# Sheet_4_nizovie.net
KiCad netlist of a schematic drawn in Altium Designer
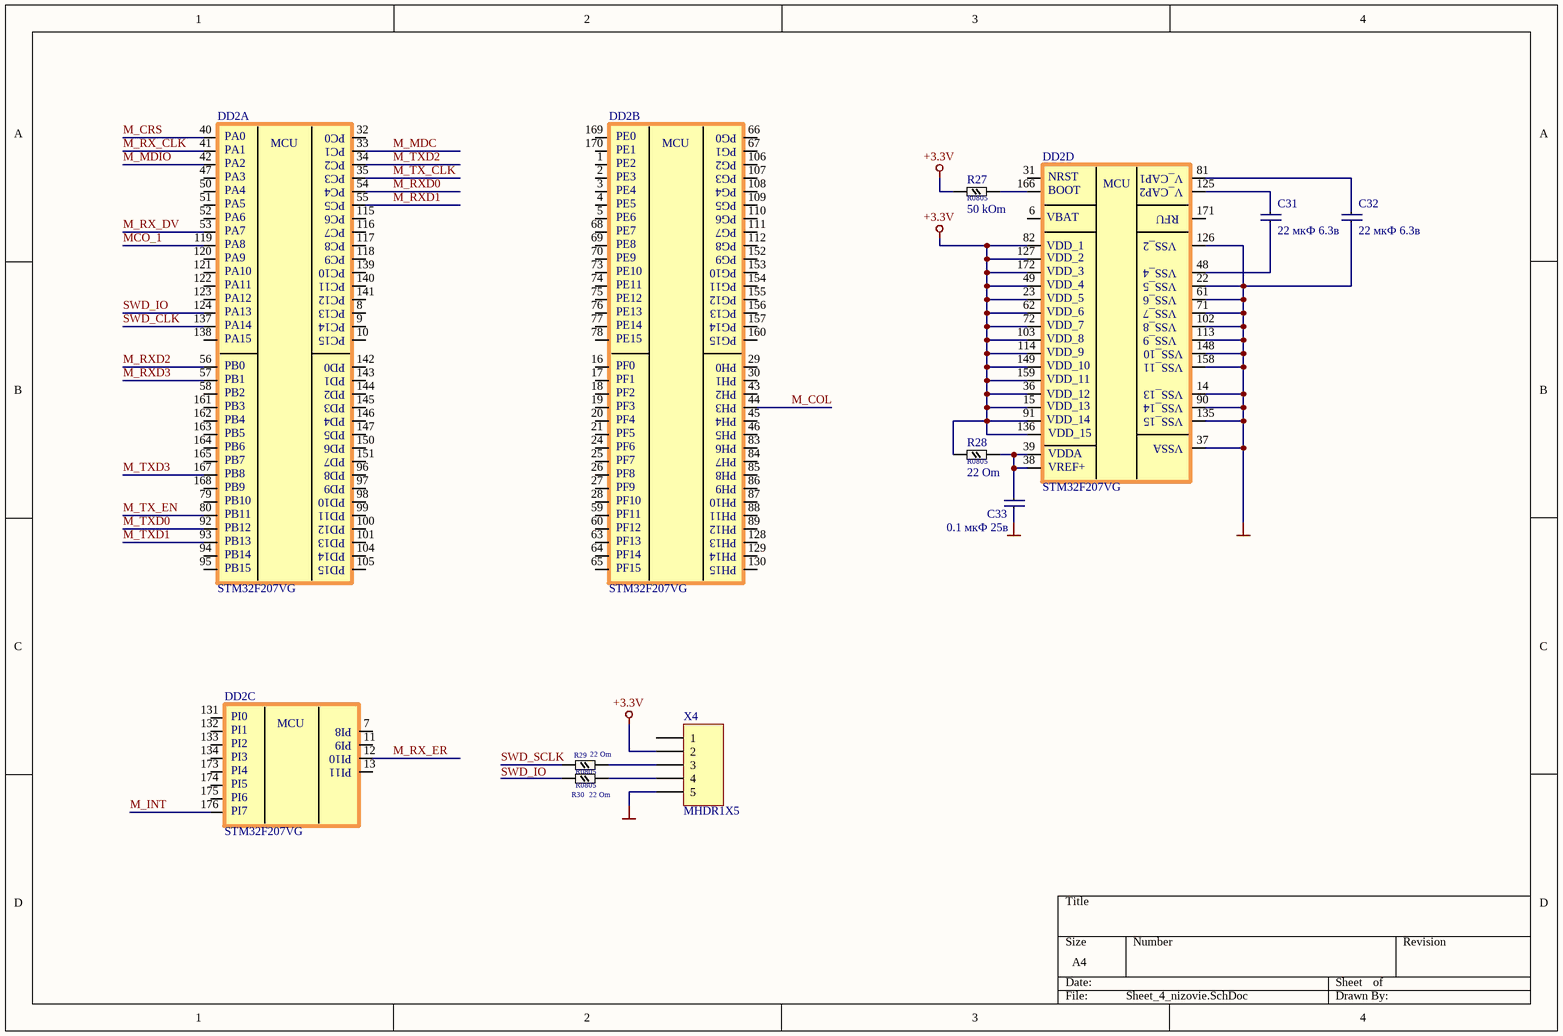
[diagram p0: Sheet_4_nizovie.SchDoc]

(export (version "E")
  (design (tool "Eeschema 10.0.6"))
  (components
    (comp (ref "C31")
      (value "22 мкФ 6.3в")
      (footprint "FP_0805")
      (libsource (lib "Schlib_nizovie") (part "C0805"))
    )
    (comp (ref "C32")
      (value "22 мкФ 6.3в")
      (footprint "FP_0805")
      (libsource (lib "Schlib_nizovie") (part "C0805"))
    )
    (comp (ref "C33")
      (value "0.1 мкФ 25в")
      (footprint "FP_0805")
      (libsource (lib "Schlib_nizovie") (part "C0805"))
    )
    (comp (ref "DD2")
      (value "STM32F207VG")
      (footprint "TSQFP50P2600X2600X160-176N")
      (description "STM32")
      (libsource (lib "Schlib_nizovie") (part "STM32D207VG"))
    )
    (comp (ref "R27")
      (value "50 kOm")
      (footprint "FP_0805")
      (libsource (lib "Schlib_nizovie") (part "R0805"))
    )
    (comp (ref "R28") (value "22 Om") (footprint "FP_0805") (libsource (lib "Schlib_nizovie") (part "R0805")))
    (comp (ref "R29") (value "22 Om") (footprint "FP_0805") (libsource (lib "Schlib_nizovie") (part "R0805")))
    (comp (ref "R30") (value "22 Om") (footprint "FP_0805") (libsource (lib "Schlib_nizovie") (part "R0805")))
    (comp (ref "X4")
      (value "MHDR1X5")
      (footprint "MHDR1X5")
      (description "Header, 5-Pin")
      (fields (field (name "PUBLISHER") "Altium Limited"))
      (libsource (lib "Miscellaneous Connectors") (part "MHDR1X5"))
    )
  )
  (nets
    (net (code "1") (name "+3.3V") (class "Default")
      (node (ref "DD2") (pin "103") (pinfunction "103_103") (pintype "passive"))
      (node (ref "DD2") (pin "114") (pinfunction "114_114") (pintype "passive"))
      (node (ref "DD2") (pin "127") (pinfunction "127_127") (pintype "passive"))
      (node (ref "DD2") (pin "136") (pinfunction "136_136") (pintype "passive"))
      (node (ref "DD2") (pin "149") (pinfunction "149_149") (pintype "passive"))
      (node (ref "DD2") (pin "15") (pinfunction "15_15") (pintype "passive"))
      (node (ref "DD2") (pin "159") (pinfunction "159_159") (pintype "passive"))
      (node (ref "DD2") (pin "172") (pinfunction "172_172") (pintype "passive"))
      (node (ref "DD2") (pin "23") (pinfunction "23_23") (pintype "passive"))
      (node (ref "DD2") (pin "36") (pinfunction "36_36") (pintype "passive"))
      (node (ref "DD2") (pin "49") (pinfunction "49_49") (pintype "passive"))
      (node (ref "DD2") (pin "62") (pinfunction "62_62") (pintype "passive"))
      (node (ref "DD2") (pin "72") (pinfunction "72_72") (pintype "passive"))
      (node (ref "DD2") (pin "82") (pinfunction "82_82") (pintype "passive"))
      (node (ref "DD2") (pin "91") (pinfunction "91_91") (pintype "passive"))
      (node (ref "R27") (pin "1") (pinfunction "1_1") (pintype "passive"))
      (node (ref "R28") (pin "1") (pinfunction "1_1") (pintype "passive"))
      (node (ref "X4") (pin "2") (pinfunction "2_2") (pintype "passive"))
    )
    (net (code "2") (name "/MCO_1") (class "Default")
      (node (ref "DD2") (pin "119") (pinfunction "119_119") (pintype "passive"))
    )
    (net (code "3") (name "/M_COL") (class "Default")
      (node (ref "DD2") (pin "44") (pinfunction "44_44") (pintype "passive"))
    )
    (net (code "4") (name "/M_CRS") (class "Default")
      (node (ref "DD2") (pin "40") (pinfunction "40_40") (pintype "passive"))
    )
    (net (code "5") (name "/M_INT") (class "Default")
      (node (ref "DD2") (pin "176") (pinfunction "176_176") (pintype "passive"))
    )
    (net (code "6") (name "/M_MDC") (class "Default")
      (node (ref "DD2") (pin "33") (pinfunction "33_33") (pintype "passive"))
    )
    (net (code "7") (name "/M_MDIO") (class "Default")
      (node (ref "DD2") (pin "42") (pinfunction "42_42") (pintype "passive"))
    )
    (net (code "8") (name "/M_RXD0") (class "Default")
      (node (ref "DD2") (pin "54") (pinfunction "54_54") (pintype "passive"))
    )
    (net (code "9") (name "/M_RXD1") (class "Default")
      (node (ref "DD2") (pin "55") (pinfunction "55_55") (pintype "passive"))
    )
    (net (code "10") (name "/M_RXD2") (class "Default")
      (node (ref "DD2") (pin "56") (pinfunction "56_56") (pintype "passive"))
    )
    (net (code "11") (name "/M_RXD3") (class "Default")
      (node (ref "DD2") (pin "57") (pinfunction "57_57") (pintype "passive"))
    )
    (net (code "12") (name "/M_RX_CLK") (class "Default")
      (node (ref "DD2") (pin "41") (pinfunction "41_41") (pintype "passive"))
    )
    (net (code "13") (name "/M_RX_DV") (class "Default")
      (node (ref "DD2") (pin "53") (pinfunction "53_53") (pintype "passive"))
    )
    (net (code "14") (name "/M_RX_ER") (class "Default")
      (node (ref "DD2") (pin "12") (pinfunction "12_12") (pintype "passive"))
    )
    (net (code "15") (name "/M_TXD0") (class "Default")
      (node (ref "DD2") (pin "92") (pinfunction "92_92") (pintype "passive"))
    )
    (net (code "16") (name "/M_TXD1") (class "Default")
      (node (ref "DD2") (pin "93") (pinfunction "93_93") (pintype "passive"))
    )
    (net (code "17") (name "/M_TXD2") (class "Default")
      (node (ref "DD2") (pin "34") (pinfunction "34_34") (pintype "passive"))
    )
    (net (code "18") (name "/M_TXD3") (class "Default")
      (node (ref "DD2") (pin "167") (pinfunction "167_167") (pintype "passive"))
    )
    (net (code "19") (name "/M_TX_CLK") (class "Default")
      (node (ref "DD2") (pin "35") (pinfunction "35_35") (pintype "passive"))
    )
    (net (code "20") (name "/M_TX_EN") (class "Default")
      (node (ref "DD2") (pin "80") (pinfunction "80_80") (pintype "passive"))
    )
    (net (code "21") (name "/SWD_CLK") (class "Default")
      (node (ref "DD2") (pin "137") (pinfunction "137_137") (pintype "passive"))
    )
    (net (code "22") (name "/SWD_IO") (class "Default")
      (node (ref "DD2") (pin "124") (pinfunction "124_124") (pintype "passive"))
    )
    (net (code "23") (name "/SWD_SCLK") (class "Default")
      (node (ref "R29") (pin "1") (pinfunction "1_1") (pintype "passive"))
    )
    (net (code "24") (name "GND") (class "Default")
      (node (ref "C32") (pin "1") (pinfunction "1_1") (pintype "passive"))
      (node (ref "C33") (pin "1") (pinfunction "1_1") (pintype "passive"))
      (node (ref "DD2") (pin "102") (pinfunction "102_102") (pintype "passive"))
      (node (ref "DD2") (pin "113") (pinfunction "113_113") (pintype "passive"))
      (node (ref "DD2") (pin "126") (pinfunction "126_126") (pintype "passive"))
      (node (ref "DD2") (pin "135") (pinfunction "135_135") (pintype "passive"))
      (node (ref "DD2") (pin "14") (pinfunction "14_14") (pintype "passive"))
      (node (ref "DD2") (pin "148") (pinfunction "148_148") (pintype "passive"))
      (node (ref "DD2") (pin "158") (pinfunction "158_158") (pintype "passive"))
      (node (ref "DD2") (pin "22") (pinfunction "22_22") (pintype "passive"))
      (node (ref "DD2") (pin "37") (pinfunction "37_37") (pintype "passive"))
      (node (ref "DD2") (pin "61") (pinfunction "61_61") (pintype "passive"))
      (node (ref "DD2") (pin "71") (pinfunction "71_71") (pintype "passive"))
      (node (ref "DD2") (pin "90") (pinfunction "90_90") (pintype "passive"))
      (node (ref "X4") (pin "5") (pinfunction "5_5") (pintype "passive"))
    )
    (net (code "25") (name "Net-(C31-Pad1)") (class "Default")
      (node (ref "C31") (pin "1") (pinfunction "1_1") (pintype "passive"))
      (node (ref "DD2") (pin "48") (pinfunction "48_48") (pintype "passive"))
    )
    (net (code "26") (name "Net-(C31-Pad2)") (class "Default")
      (node (ref "C31") (pin "2") (pinfunction "2_2") (pintype "passive"))
      (node (ref "DD2") (pin "125") (pinfunction "125_125") (pintype "passive"))
    )
    (net (code "27") (name "Net-(C32-Pad2)") (class "Default")
      (node (ref "C32") (pin "2") (pinfunction "2_2") (pintype "passive"))
      (node (ref "DD2") (pin "81") (pinfunction "81_81") (pintype "passive"))
    )
    (net (code "28") (name "Net-(C33-Pad2)") (class "Default")
      (node (ref "C33") (pin "2") (pinfunction "2_2") (pintype "passive"))
      (node (ref "DD2") (pin "38") (pinfunction "38_38") (pintype "passive"))
      (node (ref "DD2") (pin "39") (pinfunction "39_39") (pintype "passive"))
      (node (ref "R28") (pin "2") (pinfunction "2_2") (pintype "passive"))
    )
    (net (code "29") (name "Net-(DD2-Pad166)") (class "Default")
      (node (ref "DD2") (pin "166") (pinfunction "166_166") (pintype "passive"))
      (node (ref "R27") (pin "2") (pinfunction "2_2") (pintype "passive"))
    )
    (net (code "30") (name "Net-(R29-Pad2)") (class "Default")
      (node (ref "R29") (pin "2") (pinfunction "2_2") (pintype "passive"))
      (node (ref "X4") (pin "3") (pinfunction "3_3") (pintype "passive"))
    )
    (net (code "31") (name "Net-(R30-Pad2)") (class "Default")
      (node (ref "R30") (pin "2") (pinfunction "2_2") (pintype "passive"))
      (node (ref "X4") (pin "4") (pinfunction "4_4") (pintype "passive"))
    )
    (net (code "32") (name "unconnected-(DD2-Pad1)") (class "Default")
      (node (ref "DD2") (pin "1") (pinfunction "1_1") (pintype "passive"))
    )
    (net (code "33") (name "unconnected-(DD2-Pad2)") (class "Default")
      (node (ref "DD2") (pin "2") (pinfunction "2_2") (pintype "passive"))
    )
    (net (code "34") (name "unconnected-(DD2-Pad3)") (class "Default")
      (node (ref "DD2") (pin "3") (pinfunction "3_3") (pintype "passive"))
    )
    (net (code "35") (name "unconnected-(DD2-Pad4)") (class "Default")
      (node (ref "DD2") (pin "4") (pinfunction "4_4") (pintype "passive"))
    )
    (net (code "36") (name "unconnected-(DD2-Pad5)") (class "Default")
      (node (ref "DD2") (pin "5") (pinfunction "5_5") (pintype "passive"))
    )
    (net (code "37") (name "unconnected-(DD2-Pad6)") (class "Default")
      (node (ref "DD2") (pin "6") (pinfunction "6_6") (pintype "passive"))
    )
    (net (code "38") (name "unconnected-(DD2-Pad7)") (class "Default")
      (node (ref "DD2") (pin "7") (pinfunction "7_7") (pintype "passive"))
    )
    (net (code "39") (name "unconnected-(DD2-Pad8)") (class "Default")
      (node (ref "DD2") (pin "8") (pinfunction "8_8") (pintype "passive"))
    )
    (net (code "40") (name "unconnected-(DD2-Pad9)") (class "Default")
      (node (ref "DD2") (pin "9") (pinfunction "9_9") (pintype "passive"))
    )
    (net (code "41") (name "unconnected-(DD2-Pad10)") (class "Default")
      (node (ref "DD2") (pin "10") (pinfunction "10_10") (pintype "passive"))
    )
    (net (code "42") (name "unconnected-(DD2-Pad11)") (class "Default")
      (node (ref "DD2") (pin "11") (pinfunction "11_11") (pintype "passive"))
    )
    (net (code "43") (name "unconnected-(DD2-Pad13)") (class "Default")
      (node (ref "DD2") (pin "13") (pinfunction "13_13") (pintype "passive"))
    )
    (net (code "44") (name "unconnected-(DD2-Pad16)") (class "Default")
      (node (ref "DD2") (pin "16") (pinfunction "16_16") (pintype "passive"))
    )
    (net (code "45") (name "unconnected-(DD2-Pad17)") (class "Default")
      (node (ref "DD2") (pin "17") (pinfunction "17_17") (pintype "passive"))
    )
    (net (code "46") (name "unconnected-(DD2-Pad18)") (class "Default")
      (node (ref "DD2") (pin "18") (pinfunction "18_18") (pintype "passive"))
    )
    (net (code "47") (name "unconnected-(DD2-Pad19)") (class "Default")
      (node (ref "DD2") (pin "19") (pinfunction "19_19") (pintype "passive"))
    )
    (net (code "48") (name "unconnected-(DD2-Pad20)") (class "Default")
      (node (ref "DD2") (pin "20") (pinfunction "20_20") (pintype "passive"))
    )
    (net (code "49") (name "unconnected-(DD2-Pad21)") (class "Default")
      (node (ref "DD2") (pin "21") (pinfunction "21_21") (pintype "passive"))
    )
    (net (code "50") (name "unconnected-(DD2-Pad24)") (class "Default")
      (node (ref "DD2") (pin "24") (pinfunction "24_24") (pintype "passive"))
    )
    (net (code "51") (name "unconnected-(DD2-Pad25)") (class "Default")
      (node (ref "DD2") (pin "25") (pinfunction "25_25") (pintype "passive"))
    )
    (net (code "52") (name "unconnected-(DD2-Pad26)") (class "Default")
      (node (ref "DD2") (pin "26") (pinfunction "26_26") (pintype "passive"))
    )
    (net (code "53") (name "unconnected-(DD2-Pad27)") (class "Default")
      (node (ref "DD2") (pin "27") (pinfunction "27_27") (pintype "passive"))
    )
    (net (code "54") (name "unconnected-(DD2-Pad28)") (class "Default")
      (node (ref "DD2") (pin "28") (pinfunction "28_28") (pintype "passive"))
    )
    (net (code "55") (name "unconnected-(DD2-Pad29)") (class "Default")
      (node (ref "DD2") (pin "29") (pinfunction "29_29") (pintype "passive"))
    )
    (net (code "56") (name "unconnected-(DD2-Pad30)") (class "Default")
      (node (ref "DD2") (pin "30") (pinfunction "30_30") (pintype "passive"))
    )
    (net (code "57") (name "unconnected-(DD2-Pad31)") (class "Default")
      (node (ref "DD2") (pin "31") (pinfunction "31_31") (pintype "passive"))
    )
    (net (code "58") (name "unconnected-(DD2-Pad32)") (class "Default")
      (node (ref "DD2") (pin "32") (pinfunction "32_32") (pintype "passive"))
    )
    (net (code "59") (name "unconnected-(DD2-Pad43)") (class "Default")
      (node (ref "DD2") (pin "43") (pinfunction "43_43") (pintype "passive"))
    )
    (net (code "60") (name "unconnected-(DD2-Pad45)") (class "Default")
      (node (ref "DD2") (pin "45") (pinfunction "45_45") (pintype "passive"))
    )
    (net (code "61") (name "unconnected-(DD2-Pad46)") (class "Default")
      (node (ref "DD2") (pin "46") (pinfunction "46_46") (pintype "passive"))
    )
    (net (code "62") (name "unconnected-(DD2-Pad47)") (class "Default")
      (node (ref "DD2") (pin "47") (pinfunction "47_47") (pintype "passive"))
    )
    (net (code "63") (name "unconnected-(DD2-Pad50)") (class "Default")
      (node (ref "DD2") (pin "50") (pinfunction "50_50") (pintype "passive"))
    )
    (net (code "64") (name "unconnected-(DD2-Pad51)") (class "Default")
      (node (ref "DD2") (pin "51") (pinfunction "51_51") (pintype "passive"))
    )
    (net (code "65") (name "unconnected-(DD2-Pad52)") (class "Default")
      (node (ref "DD2") (pin "52") (pinfunction "52_52") (pintype "passive"))
    )
    (net (code "66") (name "unconnected-(DD2-Pad58)") (class "Default")
      (node (ref "DD2") (pin "58") (pinfunction "58_58") (pintype "passive"))
    )
    (net (code "67") (name "unconnected-(DD2-Pad59)") (class "Default")
      (node (ref "DD2") (pin "59") (pinfunction "59_59") (pintype "passive"))
    )
    (net (code "68") (name "unconnected-(DD2-Pad60)") (class "Default")
      (node (ref "DD2") (pin "60") (pinfunction "60_60") (pintype "passive"))
    )
    (net (code "69") (name "unconnected-(DD2-Pad63)") (class "Default")
      (node (ref "DD2") (pin "63") (pinfunction "63_63") (pintype "passive"))
    )
    (net (code "70") (name "unconnected-(DD2-Pad64)") (class "Default")
      (node (ref "DD2") (pin "64") (pinfunction "64_64") (pintype "passive"))
    )
    (net (code "71") (name "unconnected-(DD2-Pad65)") (class "Default")
      (node (ref "DD2") (pin "65") (pinfunction "65_65") (pintype "passive"))
    )
    (net (code "72") (name "unconnected-(DD2-Pad66)") (class "Default")
      (node (ref "DD2") (pin "66") (pinfunction "66_66") (pintype "passive"))
    )
    (net (code "73") (name "unconnected-(DD2-Pad67)") (class "Default")
      (node (ref "DD2") (pin "67") (pinfunction "67_67") (pintype "passive"))
    )
    (net (code "74") (name "unconnected-(DD2-Pad68)") (class "Default")
      (node (ref "DD2") (pin "68") (pinfunction "68_68") (pintype "passive"))
    )
    (net (code "75") (name "unconnected-(DD2-Pad69)") (class "Default")
      (node (ref "DD2") (pin "69") (pinfunction "69_69") (pintype "passive"))
    )
    (net (code "76") (name "unconnected-(DD2-Pad70)") (class "Default")
      (node (ref "DD2") (pin "70") (pinfunction "70_70") (pintype "passive"))
    )
    (net (code "77") (name "unconnected-(DD2-Pad73)") (class "Default")
      (node (ref "DD2") (pin "73") (pinfunction "73_73") (pintype "passive"))
    )
    (net (code "78") (name "unconnected-(DD2-Pad74)") (class "Default")
      (node (ref "DD2") (pin "74") (pinfunction "74_74") (pintype "passive"))
    )
    (net (code "79") (name "unconnected-(DD2-Pad75)") (class "Default")
      (node (ref "DD2") (pin "75") (pinfunction "75_75") (pintype "passive"))
    )
    (net (code "80") (name "unconnected-(DD2-Pad76)") (class "Default")
      (node (ref "DD2") (pin "76") (pinfunction "76_76") (pintype "passive"))
    )
    (net (code "81") (name "unconnected-(DD2-Pad77)") (class "Default")
      (node (ref "DD2") (pin "77") (pinfunction "77_77") (pintype "passive"))
    )
    (net (code "82") (name "unconnected-(DD2-Pad78)") (class "Default")
      (node (ref "DD2") (pin "78") (pinfunction "78_78") (pintype "passive"))
    )
    (net (code "83") (name "unconnected-(DD2-Pad79)") (class "Default")
      (node (ref "DD2") (pin "79") (pinfunction "79_79") (pintype "passive"))
    )
    (net (code "84") (name "unconnected-(DD2-Pad83)") (class "Default")
      (node (ref "DD2") (pin "83") (pinfunction "83_83") (pintype "passive"))
    )
    (net (code "85") (name "unconnected-(DD2-Pad84)") (class "Default")
      (node (ref "DD2") (pin "84") (pinfunction "84_84") (pintype "passive"))
    )
    (net (code "86") (name "unconnected-(DD2-Pad85)") (class "Default")
      (node (ref "DD2") (pin "85") (pinfunction "85_85") (pintype "passive"))
    )
    (net (code "87") (name "unconnected-(DD2-Pad86)") (class "Default")
      (node (ref "DD2") (pin "86") (pinfunction "86_86") (pintype "passive"))
    )
    (net (code "88") (name "unconnected-(DD2-Pad87)") (class "Default")
      (node (ref "DD2") (pin "87") (pinfunction "87_87") (pintype "passive"))
    )
    (net (code "89") (name "unconnected-(DD2-Pad88)") (class "Default")
      (node (ref "DD2") (pin "88") (pinfunction "88_88") (pintype "passive"))
    )
    (net (code "90") (name "unconnected-(DD2-Pad89)") (class "Default")
      (node (ref "DD2") (pin "89") (pinfunction "89_89") (pintype "passive"))
    )
    (net (code "91") (name "unconnected-(DD2-Pad94)") (class "Default")
      (node (ref "DD2") (pin "94") (pinfunction "94_94") (pintype "passive"))
    )
    (net (code "92") (name "unconnected-(DD2-Pad95)") (class "Default")
      (node (ref "DD2") (pin "95") (pinfunction "95_95") (pintype "passive"))
    )
    (net (code "93") (name "unconnected-(DD2-Pad96)") (class "Default")
      (node (ref "DD2") (pin "96") (pinfunction "96_96") (pintype "passive"))
    )
    (net (code "94") (name "unconnected-(DD2-Pad97)") (class "Default")
      (node (ref "DD2") (pin "97") (pinfunction "97_97") (pintype "passive"))
    )
    (net (code "95") (name "unconnected-(DD2-Pad98)") (class "Default")
      (node (ref "DD2") (pin "98") (pinfunction "98_98") (pintype "passive"))
    )
    (net (code "96") (name "unconnected-(DD2-Pad99)") (class "Default")
      (node (ref "DD2") (pin "99") (pinfunction "99_99") (pintype "passive"))
    )
    (net (code "97") (name "unconnected-(DD2-Pad100)") (class "Default")
      (node (ref "DD2") (pin "100") (pinfunction "100_100") (pintype "passive"))
    )
    (net (code "98") (name "unconnected-(DD2-Pad101)") (class "Default")
      (node (ref "DD2") (pin "101") (pinfunction "101_101") (pintype "passive"))
    )
    (net (code "99") (name "unconnected-(DD2-Pad104)") (class "Default")
      (node (ref "DD2") (pin "104") (pinfunction "104_104") (pintype "passive"))
    )
    (net (code "100") (name "unconnected-(DD2-Pad105)") (class "Default")
      (node (ref "DD2") (pin "105") (pinfunction "105_105") (pintype "passive"))
    )
    (net (code "101") (name "unconnected-(DD2-Pad106)") (class "Default")
      (node (ref "DD2") (pin "106") (pinfunction "106_106") (pintype "passive"))
    )
    (net (code "102") (name "unconnected-(DD2-Pad107)") (class "Default")
      (node (ref "DD2") (pin "107") (pinfunction "107_107") (pintype "passive"))
    )
    (net (code "103") (name "unconnected-(DD2-Pad108)") (class "Default")
      (node (ref "DD2") (pin "108") (pinfunction "108_108") (pintype "passive"))
    )
    (net (code "104") (name "unconnected-(DD2-Pad109)") (class "Default")
      (node (ref "DD2") (pin "109") (pinfunction "109_109") (pintype "passive"))
    )
    (net (code "105") (name "unconnected-(DD2-Pad110)") (class "Default")
      (node (ref "DD2") (pin "110") (pinfunction "110_110") (pintype "passive"))
    )
    (net (code "106") (name "unconnected-(DD2-Pad111)") (class "Default")
      (node (ref "DD2") (pin "111") (pinfunction "111_111") (pintype "passive"))
    )
    (net (code "107") (name "unconnected-(DD2-Pad112)") (class "Default")
      (node (ref "DD2") (pin "112") (pinfunction "112_112") (pintype "passive"))
    )
    (net (code "108") (name "unconnected-(DD2-Pad115)") (class "Default")
      (node (ref "DD2") (pin "115") (pinfunction "115_115") (pintype "passive"))
    )
    (net (code "109") (name "unconnected-(DD2-Pad116)") (class "Default")
      (node (ref "DD2") (pin "116") (pinfunction "116_116") (pintype "passive"))
    )
    (net (code "110") (name "unconnected-(DD2-Pad117)") (class "Default")
      (node (ref "DD2") (pin "117") (pinfunction "117_117") (pintype "passive"))
    )
    (net (code "111") (name "unconnected-(DD2-Pad118)") (class "Default")
      (node (ref "DD2") (pin "118") (pinfunction "118_118") (pintype "passive"))
    )
    (net (code "112") (name "unconnected-(DD2-Pad120)") (class "Default")
      (node (ref "DD2") (pin "120") (pinfunction "120_120") (pintype "passive"))
    )
    (net (code "113") (name "unconnected-(DD2-Pad121)") (class "Default")
      (node (ref "DD2") (pin "121") (pinfunction "121_121") (pintype "passive"))
    )
    (net (code "114") (name "unconnected-(DD2-Pad122)") (class "Default")
      (node (ref "DD2") (pin "122") (pinfunction "122_122") (pintype "passive"))
    )
    (net (code "115") (name "unconnected-(DD2-Pad123)") (class "Default")
      (node (ref "DD2") (pin "123") (pinfunction "123_123") (pintype "passive"))
    )
    (net (code "116") (name "unconnected-(DD2-Pad128)") (class "Default")
      (node (ref "DD2") (pin "128") (pinfunction "128_128") (pintype "passive"))
    )
    (net (code "117") (name "unconnected-(DD2-Pad129)") (class "Default")
      (node (ref "DD2") (pin "129") (pinfunction "129_129") (pintype "passive"))
    )
    (net (code "118") (name "unconnected-(DD2-Pad130)") (class "Default")
      (node (ref "DD2") (pin "130") (pinfunction "130_130") (pintype "passive"))
    )
    (net (code "119") (name "unconnected-(DD2-Pad131)") (class "Default")
      (node (ref "DD2") (pin "131") (pinfunction "131_131") (pintype "passive"))
    )
    (net (code "120") (name "unconnected-(DD2-Pad132)") (class "Default")
      (node (ref "DD2") (pin "132") (pinfunction "132_132") (pintype "passive"))
    )
    (net (code "121") (name "unconnected-(DD2-Pad133)") (class "Default")
      (node (ref "DD2") (pin "133") (pinfunction "133_133") (pintype "passive"))
    )
    (net (code "122") (name "unconnected-(DD2-Pad134)") (class "Default")
      (node (ref "DD2") (pin "134") (pinfunction "134_134") (pintype "passive"))
    )
    (net (code "123") (name "unconnected-(DD2-Pad138)") (class "Default")
      (node (ref "DD2") (pin "138") (pinfunction "138_138") (pintype "passive"))
    )
    (net (code "124") (name "unconnected-(DD2-Pad139)") (class "Default")
      (node (ref "DD2") (pin "139") (pinfunction "139_139") (pintype "passive"))
    )
    (net (code "125") (name "unconnected-(DD2-Pad140)") (class "Default")
      (node (ref "DD2") (pin "140") (pinfunction "140_140") (pintype "passive"))
    )
    (net (code "126") (name "unconnected-(DD2-Pad141)") (class "Default")
      (node (ref "DD2") (pin "141") (pinfunction "141_141") (pintype "passive"))
    )
    (net (code "127") (name "unconnected-(DD2-Pad142)") (class "Default")
      (node (ref "DD2") (pin "142") (pinfunction "142_142") (pintype "passive"))
    )
    (net (code "128") (name "unconnected-(DD2-Pad143)") (class "Default")
      (node (ref "DD2") (pin "143") (pinfunction "143_143") (pintype "passive"))
    )
    (net (code "129") (name "unconnected-(DD2-Pad144)") (class "Default")
      (node (ref "DD2") (pin "144") (pinfunction "144_144") (pintype "passive"))
    )
    (net (code "130") (name "unconnected-(DD2-Pad145)") (class "Default")
      (node (ref "DD2") (pin "145") (pinfunction "145_145") (pintype "passive"))
    )
    (net (code "131") (name "unconnected-(DD2-Pad146)") (class "Default")
      (node (ref "DD2") (pin "146") (pinfunction "146_146") (pintype "passive"))
    )
    (net (code "132") (name "unconnected-(DD2-Pad147)") (class "Default")
      (node (ref "DD2") (pin "147") (pinfunction "147_147") (pintype "passive"))
    )
    (net (code "133") (name "unconnected-(DD2-Pad150)") (class "Default")
      (node (ref "DD2") (pin "150") (pinfunction "150_150") (pintype "passive"))
    )
    (net (code "134") (name "unconnected-(DD2-Pad151)") (class "Default")
      (node (ref "DD2") (pin "151") (pinfunction "151_151") (pintype "passive"))
    )
    (net (code "135") (name "unconnected-(DD2-Pad152)") (class "Default")
      (node (ref "DD2") (pin "152") (pinfunction "152_152") (pintype "passive"))
    )
    (net (code "136") (name "unconnected-(DD2-Pad153)") (class "Default")
      (node (ref "DD2") (pin "153") (pinfunction "153_153") (pintype "passive"))
    )
    (net (code "137") (name "unconnected-(DD2-Pad154)") (class "Default")
      (node (ref "DD2") (pin "154") (pinfunction "154_154") (pintype "passive"))
    )
    (net (code "138") (name "unconnected-(DD2-Pad155)") (class "Default")
      (node (ref "DD2") (pin "155") (pinfunction "155_155") (pintype "passive"))
    )
    (net (code "139") (name "unconnected-(DD2-Pad156)") (class "Default")
      (node (ref "DD2") (pin "156") (pinfunction "156_156") (pintype "passive"))
    )
    (net (code "140") (name "unconnected-(DD2-Pad157)") (class "Default")
      (node (ref "DD2") (pin "157") (pinfunction "157_157") (pintype "passive"))
    )
    (net (code "141") (name "unconnected-(DD2-Pad160)") (class "Default")
      (node (ref "DD2") (pin "160") (pinfunction "160_160") (pintype "passive"))
    )
    (net (code "142") (name "unconnected-(DD2-Pad161)") (class "Default")
      (node (ref "DD2") (pin "161") (pinfunction "161_161") (pintype "passive"))
    )
    (net (code "143") (name "unconnected-(DD2-Pad162)") (class "Default")
      (node (ref "DD2") (pin "162") (pinfunction "162_162") (pintype "passive"))
    )
    (net (code "144") (name "unconnected-(DD2-Pad163)") (class "Default")
      (node (ref "DD2") (pin "163") (pinfunction "163_163") (pintype "passive"))
    )
    (net (code "145") (name "unconnected-(DD2-Pad164)") (class "Default")
      (node (ref "DD2") (pin "164") (pinfunction "164_164") (pintype "passive"))
    )
    (net (code "146") (name "unconnected-(DD2-Pad165)") (class "Default")
      (node (ref "DD2") (pin "165") (pinfunction "165_165") (pintype "passive"))
    )
    (net (code "147") (name "unconnected-(DD2-Pad168)") (class "Default")
      (node (ref "DD2") (pin "168") (pinfunction "168_168") (pintype "passive"))
    )
    (net (code "148") (name "unconnected-(DD2-Pad169)") (class "Default")
      (node (ref "DD2") (pin "169") (pinfunction "169_169") (pintype "passive"))
    )
    (net (code "149") (name "unconnected-(DD2-Pad170)") (class "Default")
      (node (ref "DD2") (pin "170") (pinfunction "170_170") (pintype "passive"))
    )
    (net (code "150") (name "unconnected-(DD2-Pad171)") (class "Default")
      (node (ref "DD2") (pin "171") (pinfunction "171_171") (pintype "passive"))
    )
    (net (code "151") (name "unconnected-(DD2-Pad173)") (class "Default")
      (node (ref "DD2") (pin "173") (pinfunction "173_173") (pintype "passive"))
    )
    (net (code "152") (name "unconnected-(DD2-Pad174)") (class "Default")
      (node (ref "DD2") (pin "174") (pinfunction "174_174") (pintype "passive"))
    )
    (net (code "153") (name "unconnected-(DD2-Pad175)") (class "Default")
      (node (ref "DD2") (pin "175") (pinfunction "175_175") (pintype "passive"))
    )
    (net (code "154") (name "unconnected-(R30-Pad1)") (class "Default")
      (node (ref "R30") (pin "1") (pinfunction "1_1") (pintype "passive"))
    )
    (net (code "155") (name "unconnected-(X4-Pad1)") (class "Default")
      (node (ref "X4") (pin "1") (pinfunction "1_1") (pintype "passive"))
    )
  )
)
